# PROC010B_Tempsensor.net
KiCad netlist of a schematic drawn in Altium Designer
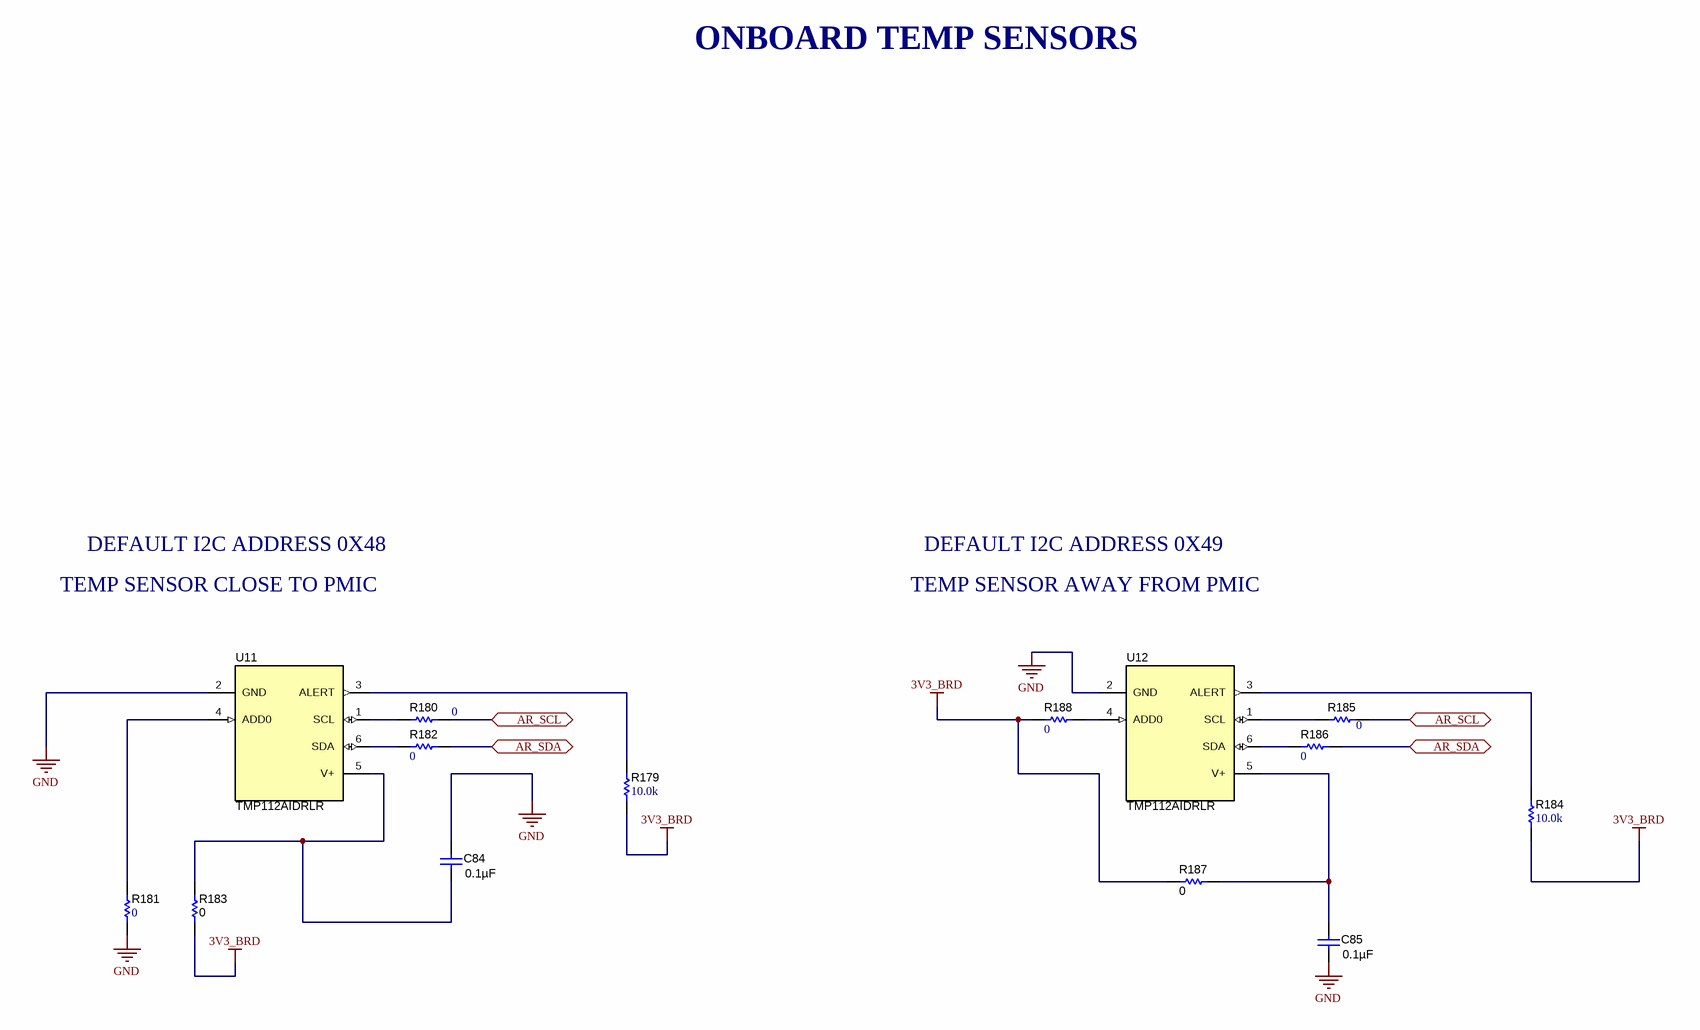
[diagram p0: PROC010B_Tempsensor.SchDoc]

(export (version "E")
  (design (tool "Eeschema 10.0.6"))
  (components
    (comp (ref "C84")
      (value "C0402C104K8RACTU")
      (footprint "0402L")
      (description "CAP, CERM, 0.1 µF, 10 V,+/- 10%, X7R, 0402")
      (fields (field (name "MANUFACTURER") "Kemet") (field (name "VALUEDISPLAYED") "0.1µF"))
      (libsource (lib "Altium Vault - TI") (part "Capacitor"))
    )
    (comp (ref "C85")
      (value "C0402C104K8RACTU")
      (footprint "0402L")
      (description "CAP, CERM, 0.1 µF, 10 V,+/- 10%, X7R, 0402")
      (fields (field (name "MANUFACTURER") "Kemet") (field (name "VALUEDISPLAYED") "0.1µF"))
      (libsource (lib "Altium Vault - TI") (part "Capacitor"))
    )
    (comp (ref "R179")
      (value "CRCW040210K0FKED")
      (footprint "0402L")
      (description "RES, 10.0 k, 1%, 0.063 W, AEC-Q200 Grade 0, 0402")
      (fields (field (name "MANUFACTURER") "Vishay-Dale") (field (name "VALUEDISPLAYED") "10.0k"))
      (libsource (lib "Altium Vault - TI") (part "Resistor"))
    )
    (comp (ref "R180")
      (value "CRCW02010000Z0ED")
      (footprint "0201_Silk")
      (description "RES, 0, 5%, 0.05 W, 0201")
      (fields (field (name "MANUFACTURER") "Vishay-Dale") (field (name "VALUEDISPLAYED") "0"))
      (libsource (lib "Altium Vault - TI") (part "Resistor"))
    )
    (comp (ref "R181")
      (value "CRCW02010000Z0ED")
      (footprint "0201_Silk")
      (description "RES, 0, 5%, 0.05 W, 0201")
      (fields (field (name "MANUFACTURER") "Vishay-Dale") (field (name "VALUEDISPLAYED") "0"))
      (libsource (lib "Altium Vault - TI") (part "Resistor"))
    )
    (comp (ref "R182")
      (value "CRCW02010000Z0ED")
      (footprint "0201_Silk")
      (description "RES, 0, 5%, 0.05 W, 0201")
      (fields (field (name "MANUFACTURER") "Vishay-Dale") (field (name "VALUEDISPLAYED") "0"))
      (libsource (lib "Altium Vault - TI") (part "Resistor"))
    )
    (comp (ref "R183")
      (value "ERJ-2GE0R00X")
      (footprint "0402L")
      (description "RES, 0, 5%, 0.063 W, 0402")
      (fields
        (field (name "MANUFACTURER") "Panasonic")
        (field (name "VALUEDISPLAYED") "0")
        (field (name "PUBLISHER") "Texas Instruments")
      )
      (libsource (lib "Altium Vault - TI") (part "Resistor"))
    )
    (comp (ref "R184")
      (value "CRCW040210K0FKED")
      (footprint "0402L")
      (description "RES, 10.0 k, 1%, 0.063 W, AEC-Q200 Grade 0, 0402")
      (fields (field (name "MANUFACTURER") "Vishay-Dale") (field (name "VALUEDISPLAYED") "10.0k"))
      (libsource (lib "Altium Vault - TI") (part "Resistor"))
    )
    (comp (ref "R185")
      (value "CRCW02010000Z0ED")
      (footprint "0201_Silk")
      (description "RES, 0, 5%, 0.05 W, 0201")
      (fields (field (name "MANUFACTURER") "Vishay-Dale") (field (name "VALUEDISPLAYED") "0"))
      (libsource (lib "Altium Vault - TI") (part "Resistor"))
    )
    (comp (ref "R186")
      (value "CRCW02010000Z0ED")
      (footprint "0201_Silk")
      (description "RES, 0, 5%, 0.05 W, 0201")
      (fields (field (name "MANUFACTURER") "Vishay-Dale") (field (name "VALUEDISPLAYED") "0"))
      (libsource (lib "Altium Vault - TI") (part "Resistor"))
    )
    (comp (ref "R187")
      (value "ERJ-2GE0R00X")
      (footprint "0402L")
      (description "RES, 0, 5%, 0.063 W, 0402")
      (fields
        (field (name "MANUFACTURER") "Panasonic")
        (field (name "VALUEDISPLAYED") "0")
        (field (name "PUBLISHER") "Texas Instruments")
      )
      (libsource (lib "Altium Vault - TI") (part "Resistor"))
    )
    (comp (ref "R188")
      (value "CRCW02010000Z0ED")
      (footprint "0201_Silk")
      (description "RES, 0, 5%, 0.05 W, 0201")
      (fields (field (name "MANUFACTURER") "Vishay-Dale") (field (name "VALUEDISPLAYED") "0"))
      (libsource (lib "Altium Vault - TI") (part "Resistor"))
    )
    (comp (ref "U11")
      (value "TMP112AIDRLR")
      (footprint "DRL0006A")
      (fields
        (field (name "ALTERNATE PARTNUMBER") "TMP112AIDRLT")
        (field (name "MANUFACTURER") "Texas Instruments")
        (field (name "PARTNUMBER") "TMP112AIDRLR")
        (field (name "PUBLISHER") "Texas Instruments")
      )
      (libsource (lib "Altium Vault - TI") (part "TMP112"))
    )
    (comp (ref "U12")
      (value "TMP112AIDRLR")
      (footprint "DRL0006A")
      (fields
        (field (name "ALTERNATE PARTNUMBER") "TMP112AIDRLT")
        (field (name "MANUFACTURER") "Texas Instruments")
        (field (name "PARTNUMBER") "TMP112AIDRLR")
        (field (name "PUBLISHER") "Texas Instruments")
      )
      (libsource (lib "Altium Vault - TI") (part "CMP-0067397-2"))
    )
  )
  (nets
    (net (code "1") (name "/AR_SCL") (class "Default")
      (node (ref "R180") (pin "1") (pinfunction "1_1") (pintype "passive"))
      (node (ref "R185") (pin "1") (pinfunction "1_1") (pintype "passive"))
    )
    (net (code "2") (name "/AR_SDA") (class "Default")
      (node (ref "R182") (pin "2") (pinfunction "2_2") (pintype "passive"))
      (node (ref "R186") (pin "2") (pinfunction "2_2") (pintype "passive"))
    )
    (net (code "3") (name "3V3_BRD") (class "Default")
      (node (ref "R179") (pin "2") (pinfunction "2_2") (pintype "passive"))
      (node (ref "R183") (pin "2") (pinfunction "2_2") (pintype "passive"))
      (node (ref "R184") (pin "2") (pinfunction "2_2") (pintype "passive"))
      (node (ref "R187") (pin "2") (pinfunction "2_2") (pintype "passive"))
      (node (ref "R188") (pin "1") (pinfunction "1_1") (pintype "passive"))
    )
    (net (code "4") (name "GND") (class "Default")
      (node (ref "C84") (pin "1") (pinfunction "1_1") (pintype "passive"))
      (node (ref "C85") (pin "2") (pinfunction "2_2") (pintype "passive"))
      (node (ref "R181") (pin "2") (pinfunction "2_2") (pintype "passive"))
      (node (ref "U11") (pin "2") (pinfunction "GND_2") (pintype "power_in"))
      (node (ref "U12") (pin "2") (pinfunction "GND_2") (pintype "power_in"))
    )
    (net (code "5") (name "Net-(U11-ADD0)") (class "Default")
      (node (ref "R181") (pin "1") (pinfunction "1_1") (pintype "passive"))
      (node (ref "U11") (pin "4") (pinfunction "ADD0_4") (pintype "input"))
    )
    (net (code "6") (name "Net-(U11-ALERT)") (class "Default")
      (node (ref "R179") (pin "1") (pinfunction "1_1") (pintype "passive"))
      (node (ref "U11") (pin "3") (pinfunction "ALERT_3") (pintype "output"))
    )
    (net (code "7") (name "Net-(U11-SCL)") (class "Default")
      (node (ref "R180") (pin "2") (pinfunction "2_2") (pintype "passive"))
      (node (ref "U11") (pin "1") (pinfunction "SCL_1") (pintype "bidirectional"))
    )
    (net (code "8") (name "Net-(U11-SDA)") (class "Default")
      (node (ref "R182") (pin "1") (pinfunction "1_1") (pintype "passive"))
      (node (ref "U11") (pin "6") (pinfunction "SDA_6") (pintype "bidirectional"))
    )
    (net (code "9") (name "Net-(U11-V+)") (class "Default")
      (node (ref "C84") (pin "2") (pinfunction "2_2") (pintype "passive"))
      (node (ref "R183") (pin "1") (pinfunction "1_1") (pintype "passive"))
      (node (ref "U11") (pin "5") (pinfunction "V+_5") (pintype "power_in"))
    )
    (net (code "10") (name "Net-(U12-ADD0)") (class "Default")
      (node (ref "R188") (pin "2") (pinfunction "2_2") (pintype "passive"))
      (node (ref "U12") (pin "4") (pinfunction "ADD0_4") (pintype "input"))
    )
    (net (code "11") (name "Net-(U12-ALERT)") (class "Default")
      (node (ref "R184") (pin "1") (pinfunction "1_1") (pintype "passive"))
      (node (ref "U12") (pin "3") (pinfunction "ALERT_3") (pintype "output"))
    )
    (net (code "12") (name "Net-(U12-SCL)") (class "Default")
      (node (ref "R185") (pin "2") (pinfunction "2_2") (pintype "passive"))
      (node (ref "U12") (pin "1") (pinfunction "SCL_1") (pintype "bidirectional"))
    )
    (net (code "13") (name "Net-(U12-SDA)") (class "Default")
      (node (ref "R186") (pin "1") (pinfunction "1_1") (pintype "passive"))
      (node (ref "U12") (pin "6") (pinfunction "SDA_6") (pintype "bidirectional"))
    )
    (net (code "14") (name "Net-(U12-V+)") (class "Default")
      (node (ref "C85") (pin "1") (pinfunction "1_1") (pintype "passive"))
      (node (ref "R187") (pin "1") (pinfunction "1_1") (pintype "passive"))
      (node (ref "U12") (pin "5") (pinfunction "V+_5") (pintype "power_in"))
    )
  )
)
